# iupitter_v0_95_rev6_161019.net
KiCad netlist of a schematic drawn in EAGLE
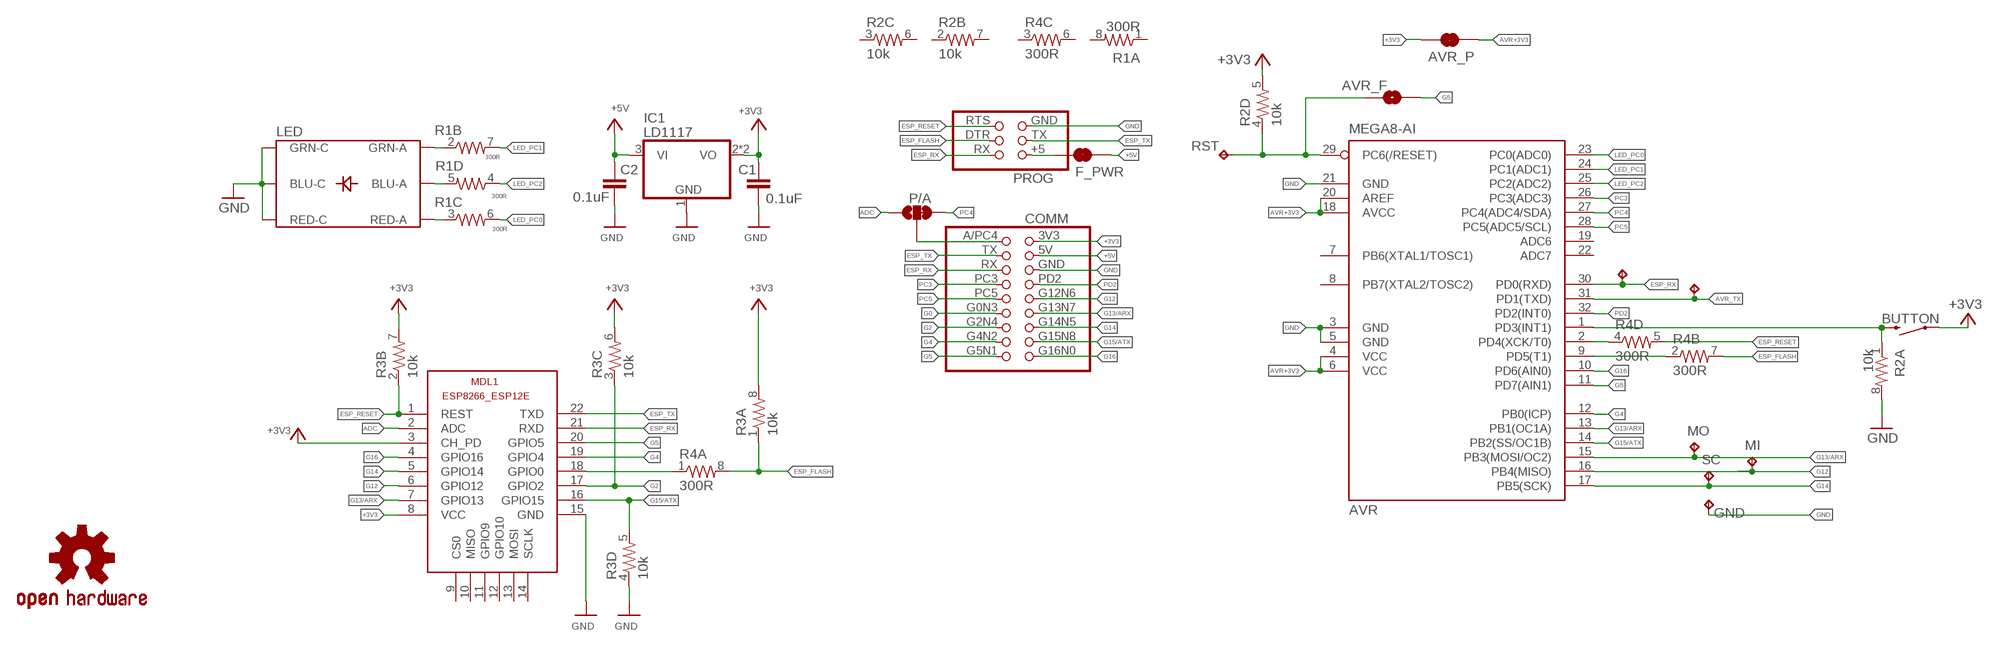
[diagram p0: schematic, sheet 1]

(export (version "E")
  (design (tool "Eeschema 10.0.6"))
  (components
    (comp (ref "ARX")
      (value "TPTP10SQ")
      (footprint "eagle-import:TP10SQ")
      (libsource (lib "eagle-import") (part "TPTP10SQ"))
    )
    (comp (ref "ATX")
      (value "TPTP10SQ")
      (footprint "eagle-import:TP10SQ")
      (libsource (lib "eagle-import") (part "TPTP10SQ"))
    )
    (comp (ref "AVR")
      (value "MEGA8-AI")
      (footprint "eagle-import:TQFP32-08")
      (fields (field (name "MPN") "ATMEGA8-16AU"))
      (libsource (lib "eagle-import") (part "MEGA8-AI"))
    )
    (comp (ref "AVR_F")
      (value "JUMPER-PAD-2-NOYES_SILK")
      (footprint "eagle-import:PAD-JUMPER-2-NO_YES_SILK")
      (libsource (lib "eagle-import") (part "JUMPER-PAD-2-NOYES_SILK"))
    )
    (comp (ref "AVR_P")
      (value "JUMPER-PAD-2-NC_BY_TRACE")
      (footprint "eagle-import:PAD-JUMPER-2-NC_BY_TRACE_YES_SILK")
      (libsource (lib "eagle-import") (part "JUMPER-PAD-2-NC_BY_TRACE"))
    )
    (comp (ref "BUTTON")
      (value "IT-1181A")
      (footprint "eagle-import:TACTILE-SWITCH-1101NE")
      (libsource (lib "eagle-import") (part "SWITCH-MOMENTARY-2SMD-1101NE"))
    )
    (comp (ref "C1")
      (value "0.1uF")
      (footprint "eagle-import:C1206")
      (libsource (lib "eagle-import") (part "C-EUC1206"))
    )
    (comp (ref "C2")
      (value "0.1uF")
      (footprint "eagle-import:C1206")
      (libsource (lib "eagle-import") (part "C-EUC1206"))
    )
    (comp (ref "COMM")
      (value "COMM_V2RIGHT")
      (footprint "eagle-import:COMM_V2_R(MAIN)")
      (libsource (lib "eagle-import") (part "COMM_V2RIGHT"))
    )
    (comp (ref "F_PWR")
      (value "JUMPER-PAD-2-NC_BY_TRACE")
      (footprint "eagle-import:PAD-JUMPER-2-NC_BY_TRACE_YES_SILK")
      (libsource (lib "eagle-import") (part "JUMPER-PAD-2-NC_BY_TRACE"))
    )
    (comp (ref "GND")
      (value "TPTP10SQ")
      (footprint "eagle-import:TP10SQ")
      (libsource (lib "eagle-import") (part "TPTP10SQ"))
    )
    (comp (ref "IC1")
      (value "LD1117")
      (footprint "eagle-import:SOT223")
      (libsource (lib "eagle-import") (part "LD1117"))
    )
    (comp (ref "LED")
      (value "LED-TRICOLOR-5050NO_IC")
      (footprint "eagle-import:LED-TRICOLOR-5050")
      (libsource (lib "eagle-import") (part "LED-TRICOLOR-5050NO_IC"))
    )
    (comp (ref "LOGO1")
      (value "OSHW-LOGOS-COPPER")
      (footprint "eagle-import:OSHW-LOGO-S_COPPER")
      (libsource (lib "eagle-import") (part "OSHW-LOGOS-COPPER"))
    )
    (comp (ref "MDL1")
      (value "ESP8266-12EESP8266-ESP12E")
      (footprint "eagle-import:ESP8266-ESP12E")
      (libsource (lib "eagle-import") (part "ESP8266-12EESP8266-ESP12E"))
    )
    (comp (ref "MI")
      (value "TPTP10SQ")
      (footprint "eagle-import:TP10SQ")
      (libsource (lib "eagle-import") (part "TPTP10SQ"))
    )
    (comp (ref "MO")
      (value "TPTP10SQ")
      (footprint "eagle-import:TP10SQ")
      (libsource (lib "eagle-import") (part "TPTP10SQ"))
    )
    (comp (ref "P/A")
      (value "JUMPER-PAD-3-2OF3_NC_BY_TRACE_SMALL")
      (footprint "eagle-import:PAD-JUMPER-3-2OF3_NC_BY_TRACE_YES_SILK_FULL_BOX")
      (libsource (lib "eagle-import") (part "JUMPER-PAD-3-2OF3_NC_BY_TRACE_SMALL"))
    )
    (comp (ref "PROG")
      (value "FLASH")
      (footprint "eagle-import:FLASH")
      (libsource (lib "eagle-import") (part "FLASH"))
    )
    (comp (ref "R1")
      (value "300R")
      (footprint "eagle-import:0603-ARV")
      (libsource (lib "eagle-import") (part "RESISTOR-ARRAY0603-ARV"))
    )
    (comp (ref "R2")
      (value "10k")
      (footprint "eagle-import:0603-ARV")
      (libsource (lib "eagle-import") (part "RESISTOR-ARRAY0603-ARV"))
    )
    (comp (ref "R3")
      (value "10k")
      (footprint "eagle-import:0603-ARV")
      (libsource (lib "eagle-import") (part "RESISTOR-ARRAY0603-ARV"))
    )
    (comp (ref "R4")
      (value "300R")
      (footprint "eagle-import:0603-ARV")
      (libsource (lib "eagle-import") (part "RESISTOR-ARRAY0603-ARV"))
    )
    (comp (ref "RST")
      (value "TPTP10SQ")
      (footprint "eagle-import:TP10SQ")
      (libsource (lib "eagle-import") (part "TPTP10SQ"))
    )
    (comp (ref "SC")
      (value "TPTP10SQ")
      (footprint "eagle-import:TP10SQ")
      (libsource (lib "eagle-import") (part "TPTP10SQ"))
    )
  )
  (nets
    (net (code "1") (name "+3V3") (class "Default")
      (node (ref "AVR_P") (pin "1") (pinfunction "1_1") (pintype "passive"))
      (node (ref "BUTTON") (pin "1") (pinfunction "1_1") (pintype "passive"))
      (node (ref "C1") (pin "1") (pinfunction "1_1") (pintype "passive"))
      (node (ref "COMM") (pin "3V3") (pinfunction "+3V3_3V3") (pintype "passive"))
      (node (ref "IC1") (pin "2") (pinfunction "VO_2") (pintype "passive"))
      (node (ref "IC1") (pin "4") (pinfunction "VO_4") (pintype "passive"))
      (node (ref "MDL1") (pin "3") (pinfunction "CH_PD_3") (pintype "bidirectional"))
      (node (ref "MDL1") (pin "8") (pinfunction "VCC_8") (pintype "bidirectional"))
      (node (ref "R2") (pin "5") (pinfunction "2_5") (pintype "passive"))
      (node (ref "R3") (pin "6") (pinfunction "2_6") (pintype "passive"))
      (node (ref "R3") (pin "7") (pinfunction "2_7") (pintype "passive"))
      (node (ref "R3") (pin "8") (pinfunction "2_8") (pintype "passive"))
    )
    (net (code "2") (name "+5V") (class "Default")
      (node (ref "C2") (pin "1") (pinfunction "1_1") (pintype "passive"))
      (node (ref "COMM") (pin "5V") (pinfunction "+5_5V") (pintype "passive"))
      (node (ref "F_PWR") (pin "2") (pinfunction "2_2") (pintype "passive"))
      (node (ref "IC1") (pin "3") (pinfunction "VI_3") (pintype "input"))
    )
    (net (code "3") (name "ADC") (class "Default")
      (node (ref "MDL1") (pin "2") (pinfunction "ADC_2") (pintype "bidirectional"))
      (node (ref "P/A") (pin "1") (pinfunction "1_1") (pintype "passive"))
    )
    (net (code "4") (name "AVR+3V3") (class "Default")
      (node (ref "AVR") (pin "18") (pinfunction "AVCC_18") (pintype "power_in"))
      (node (ref "AVR") (pin "20") (pinfunction "AREF_20") (pintype "passive"))
      (node (ref "AVR") (pin "4") (pinfunction "VCC_4") (pintype "power_in"))
      (node (ref "AVR") (pin "6") (pinfunction "VCC_6") (pintype "power_in"))
      (node (ref "AVR_P") (pin "2") (pinfunction "2_2") (pintype "passive"))
    )
    (net (code "5") (name "AVR_TX") (class "Default")
      (node (ref "ATX") (pin "TP") (pinfunction "TP_TP") (pintype "input"))
      (node (ref "AVR") (pin "31") (pinfunction "PD1(TXD)_31") (pintype "bidirectional"))
    )
    (net (code "6") (name "ESP_FLASH") (class "Default")
      (node (ref "PROG") (pin "DTR") (pinfunction "4_DTR") (pintype "passive"))
      (node (ref "R3") (pin "1") (pinfunction "1_1") (pintype "passive"))
      (node (ref "R4") (pin "7") (pinfunction "2_7") (pintype "passive"))
      (node (ref "R4") (pin "8") (pinfunction "2_8") (pintype "passive"))
    )
    (net (code "7") (name "ESP_RESET") (class "Default")
      (node (ref "MDL1") (pin "1") (pinfunction "REST_1") (pintype "bidirectional"))
      (node (ref "PROG") (pin "RTS") (pinfunction "6_RTS") (pintype "passive"))
      (node (ref "R3") (pin "2") (pinfunction "1_2") (pintype "passive"))
      (node (ref "R4") (pin "5") (pinfunction "2_5") (pintype "passive"))
    )
    (net (code "8") (name "ESP_RX") (class "Default")
      (node (ref "ARX") (pin "TP") (pinfunction "TP_TP") (pintype "input"))
      (node (ref "AVR") (pin "30") (pinfunction "PD0(RXD)_30") (pintype "bidirectional"))
      (node (ref "COMM") (pin "RX") (pinfunction "RX_RX") (pintype "passive"))
      (node (ref "MDL1") (pin "21") (pinfunction "RXD_21") (pintype "bidirectional"))
      (node (ref "PROG") (pin "RX") (pinfunction "2_RX") (pintype "passive"))
    )
    (net (code "9") (name "ESP_TX") (class "Default")
      (node (ref "COMM") (pin "TX") (pinfunction "TX_TX") (pintype "passive"))
      (node (ref "MDL1") (pin "22") (pinfunction "TXD_22") (pintype "bidirectional"))
      (node (ref "PROG") (pin "TX") (pinfunction "3_TX") (pintype "passive"))
    )
    (net (code "10") (name "G0") (class "Default")
      (node (ref "COMM") (pin "G0N3") (pinfunction "G0N3_G0N3") (pintype "passive"))
      (node (ref "MDL1") (pin "18") (pinfunction "GPIO0_18") (pintype "bidirectional"))
      (node (ref "R4") (pin "1") (pinfunction "1_1") (pintype "passive"))
    )
    (net (code "11") (name "G2") (class "Default")
      (node (ref "COMM") (pin "G2N4") (pinfunction "G2N4_G2N4") (pintype "passive"))
      (node (ref "MDL1") (pin "17") (pinfunction "GPIO2_17") (pintype "bidirectional"))
      (node (ref "R3") (pin "3") (pinfunction "1_3") (pintype "passive"))
    )
    (net (code "12") (name "G4") (class "Default")
      (node (ref "AVR") (pin "12") (pinfunction "PB0(ICP)_12") (pintype "bidirectional"))
      (node (ref "COMM") (pin "G4N2") (pinfunction "G4N2_G4N2") (pintype "passive"))
      (node (ref "MDL1") (pin "19") (pinfunction "GPIO4_19") (pintype "bidirectional"))
    )
    (net (code "13") (name "G5") (class "Default")
      (node (ref "AVR") (pin "11") (pinfunction "PD7(AIN1)_11") (pintype "bidirectional"))
      (node (ref "AVR_F") (pin "2") (pinfunction "2_2") (pintype "passive"))
      (node (ref "COMM") (pin "G5N1") (pinfunction "G5N1_G5N1") (pintype "passive"))
      (node (ref "MDL1") (pin "20") (pinfunction "GPIO5_20") (pintype "bidirectional"))
    )
    (net (code "14") (name "G12") (class "Default")
      (node (ref "AVR") (pin "16") (pinfunction "PB4(MISO)_16") (pintype "bidirectional"))
      (node (ref "COMM") (pin "G12N6") (pinfunction "G12N6_G12N6") (pintype "passive"))
      (node (ref "MDL1") (pin "6") (pinfunction "GPIO12_6") (pintype "bidirectional"))
      (node (ref "MI") (pin "TP") (pinfunction "TP_TP") (pintype "input"))
    )
    (net (code "15") (name "G13{slash}ARX") (class "Default")
      (node (ref "AVR") (pin "13") (pinfunction "PB1(OC1A)_13") (pintype "bidirectional"))
      (node (ref "AVR") (pin "15") (pinfunction "PB3(MOSI/OC2)_15") (pintype "bidirectional"))
      (node (ref "COMM") (pin "G13N7") (pinfunction "G13N7_G13N7") (pintype "passive"))
      (node (ref "MDL1") (pin "7") (pinfunction "GPIO13_7") (pintype "bidirectional"))
      (node (ref "MO") (pin "TP") (pinfunction "TP_TP") (pintype "input"))
    )
    (net (code "16") (name "G14") (class "Default")
      (node (ref "AVR") (pin "17") (pinfunction "PB5(SCK)_17") (pintype "bidirectional"))
      (node (ref "COMM") (pin "G14N5") (pinfunction "G14N5_G14N5") (pintype "passive"))
      (node (ref "MDL1") (pin "5") (pinfunction "GPIO14_5") (pintype "bidirectional"))
      (node (ref "SC") (pin "TP") (pinfunction "TP_TP") (pintype "input"))
    )
    (net (code "17") (name "G15{slash}ATX") (class "Default")
      (node (ref "AVR") (pin "14") (pinfunction "PB2(SS/OC1B)_14") (pintype "bidirectional"))
      (node (ref "COMM") (pin "G15N8") (pinfunction "G15N8_G15N8") (pintype "passive"))
      (node (ref "MDL1") (pin "16") (pinfunction "GPIO15_16") (pintype "bidirectional"))
      (node (ref "R3") (pin "5") (pinfunction "2_5") (pintype "passive"))
    )
    (net (code "18") (name "G16") (class "Default")
      (node (ref "AVR") (pin "10") (pinfunction "PD6(AIN0)_10") (pintype "bidirectional"))
      (node (ref "COMM") (pin "G16N0") (pinfunction "G16N0_G16N0") (pintype "passive"))
      (node (ref "MDL1") (pin "4") (pinfunction "GPIO16_4") (pintype "bidirectional"))
    )
    (net (code "19") (name "GND") (class "Default")
      (node (ref "AVR") (pin "21") (pinfunction "GND_21") (pintype "power_in"))
      (node (ref "AVR") (pin "3") (pinfunction "GND_3") (pintype "power_in"))
      (node (ref "AVR") (pin "5") (pinfunction "GND_5") (pintype "power_in"))
      (node (ref "C1") (pin "2") (pinfunction "2_2") (pintype "passive"))
      (node (ref "C2") (pin "2") (pinfunction "2_2") (pintype "passive"))
      (node (ref "COMM") (pin "GND") (pinfunction "GND_GND") (pintype "passive"))
      (node (ref "GND") (pin "TP") (pinfunction "TP_TP") (pintype "input"))
      (node (ref "IC1") (pin "1") (pinfunction "GND_1") (pintype "passive"))
      (node (ref "LED") (pin "4") (pinfunction "GRN-C_4") (pintype "bidirectional"))
      (node (ref "LED") (pin "5") (pinfunction "RED-C_5") (pintype "bidirectional"))
      (node (ref "LED") (pin "6") (pinfunction "BLU-C_6") (pintype "bidirectional"))
      (node (ref "MDL1") (pin "15") (pinfunction "GND_15") (pintype "bidirectional"))
      (node (ref "PROG") (pin "GND") (pinfunction "5_GND") (pintype "passive"))
      (node (ref "R2") (pin "8") (pinfunction "2_8") (pintype "passive"))
      (node (ref "R3") (pin "4") (pinfunction "1_4") (pintype "passive"))
    )
    (net (code "20") (name "LED_PC0") (class "Default")
      (node (ref "AVR") (pin "23") (pinfunction "PC0(ADC0)_23") (pintype "bidirectional"))
      (node (ref "R1") (pin "6") (pinfunction "2_6") (pintype "passive"))
    )
    (net (code "21") (name "LED_PC1") (class "Default")
      (node (ref "AVR") (pin "24") (pinfunction "PC1(ADC1)_24") (pintype "bidirectional"))
      (node (ref "R1") (pin "7") (pinfunction "2_7") (pintype "passive"))
    )
    (net (code "22") (name "LED_PC2") (class "Default")
      (node (ref "AVR") (pin "25") (pinfunction "PC2(ADC2)_25") (pintype "bidirectional"))
      (node (ref "R1") (pin "4") (pinfunction "1_4") (pintype "passive"))
    )
    (net (code "23") (name "Net-(AVR-PC6({slash}RESET))") (class "Default")
      (node (ref "AVR") (pin "29") (pinfunction "PC6(/RESET)_29") (pintype "bidirectional"))
      (node (ref "AVR_F") (pin "1") (pinfunction "1_1") (pintype "passive"))
      (node (ref "R2") (pin "4") (pinfunction "1_4") (pintype "passive"))
      (node (ref "RST") (pin "TP") (pinfunction "TP_TP") (pintype "input"))
    )
    (net (code "24") (name "Net-(AVR-PD3(INT1))") (class "Default")
      (node (ref "AVR") (pin "1") (pinfunction "PD3(INT1)_1") (pintype "bidirectional"))
      (node (ref "BUTTON") (pin "2") (pinfunction "2_2") (pintype "passive"))
      (node (ref "R2") (pin "1") (pinfunction "1_1") (pintype "passive"))
    )
    (net (code "25") (name "Net-(AVR-PD4(XCK{slash}T0))") (class "Default")
      (node (ref "AVR") (pin "2") (pinfunction "PD4(XCK/T0)_2") (pintype "bidirectional"))
      (node (ref "R4") (pin "4") (pinfunction "1_4") (pintype "passive"))
    )
    (net (code "26") (name "Net-(AVR-PD5(T1))") (class "Default")
      (node (ref "AVR") (pin "9") (pinfunction "PD5(T1)_9") (pintype "bidirectional"))
      (node (ref "R4") (pin "2") (pinfunction "1_2") (pintype "passive"))
    )
    (net (code "27") (name "Net-(COMM-ADC_PC4)") (class "Default")
      (node (ref "COMM") (pin "A/PC4") (pinfunction "ADC_PC4_A/PC4") (pintype "passive"))
      (node (ref "P/A") (pin "2") (pinfunction "2_2") (pintype "passive"))
    )
    (net (code "28") (name "Net-(LED-BLU-A)") (class "Default")
      (node (ref "LED") (pin "1") (pinfunction "BLU-A_1") (pintype "bidirectional"))
      (node (ref "R1") (pin "5") (pinfunction "2_5") (pintype "passive"))
    )
    (net (code "29") (name "Net-(LED-GRN-A)") (class "Default")
      (node (ref "LED") (pin "3") (pinfunction "GRN-A_3") (pintype "bidirectional"))
      (node (ref "R1") (pin "2") (pinfunction "1_2") (pintype "passive"))
    )
    (net (code "30") (name "Net-(LED-RED-A)") (class "Default")
      (node (ref "LED") (pin "2") (pinfunction "RED-A_2") (pintype "bidirectional"))
      (node (ref "R1") (pin "3") (pinfunction "1_3") (pintype "passive"))
    )
    (net (code "31") (name "Net-(PROG-1)") (class "Default")
      (node (ref "F_PWR") (pin "1") (pinfunction "1_1") (pintype "passive"))
      (node (ref "PROG") (pin "+5") (pinfunction "1_+5") (pintype "passive"))
    )
    (net (code "32") (name "PC3") (class "Default")
      (node (ref "AVR") (pin "26") (pinfunction "PC3(ADC3)_26") (pintype "bidirectional"))
      (node (ref "COMM") (pin "PC3") (pinfunction "PC3_PC3") (pintype "passive"))
    )
    (net (code "33") (name "PC4") (class "Default")
      (node (ref "AVR") (pin "27") (pinfunction "PC4(ADC4/SDA)_27") (pintype "bidirectional"))
      (node (ref "P/A") (pin "3") (pinfunction "3_3") (pintype "passive"))
    )
    (net (code "34") (name "PC5") (class "Default")
      (node (ref "AVR") (pin "28") (pinfunction "PC5(ADC5/SCL)_28") (pintype "bidirectional"))
      (node (ref "COMM") (pin "PC5") (pinfunction "PC4_PC5") (pintype "passive"))
    )
    (net (code "35") (name "PD2") (class "Default")
      (node (ref "AVR") (pin "32") (pinfunction "PD2(INT0)_32") (pintype "bidirectional"))
      (node (ref "COMM") (pin "PD2") (pinfunction "PD2_PD2") (pintype "passive"))
    )
    (net (code "36") (name "unconnected-(AVR-ADC6-Pad19)") (class "Default")
      (node (ref "AVR") (pin "19") (pinfunction "ADC6_19") (pintype "bidirectional"))
    )
    (net (code "37") (name "unconnected-(AVR-ADC7-Pad22)") (class "Default")
      (node (ref "AVR") (pin "22") (pinfunction "ADC7_22") (pintype "bidirectional"))
    )
    (net (code "38") (name "unconnected-(AVR-PB6(XTAL1{slash}TOSC1)-Pad7)") (class "Default")
      (node (ref "AVR") (pin "7") (pinfunction "PB6(XTAL1/TOSC1)_7") (pintype "bidirectional"))
    )
    (net (code "39") (name "unconnected-(AVR-PB7(XTAL2{slash}TOSC2)-Pad8)") (class "Default")
      (node (ref "AVR") (pin "8") (pinfunction "PB7(XTAL2/TOSC2)_8") (pintype "bidirectional"))
    )
    (net (code "40") (name "unconnected-(MDL1-CS0-Pad9)") (class "Default")
      (node (ref "MDL1") (pin "9") (pinfunction "CS0_9") (pintype "bidirectional"))
    )
    (net (code "41") (name "unconnected-(MDL1-GPIO9-Pad11)") (class "Default")
      (node (ref "MDL1") (pin "11") (pinfunction "GPIO9_11") (pintype "bidirectional"))
    )
    (net (code "42") (name "unconnected-(MDL1-GPIO10-Pad12)") (class "Default")
      (node (ref "MDL1") (pin "12") (pinfunction "GPIO10_12") (pintype "bidirectional"))
    )
    (net (code "43") (name "unconnected-(MDL1-MISO-Pad10)") (class "Default")
      (node (ref "MDL1") (pin "10") (pinfunction "MISO_10") (pintype "bidirectional"))
    )
    (net (code "44") (name "unconnected-(MDL1-MOSI-Pad13)") (class "Default")
      (node (ref "MDL1") (pin "13") (pinfunction "MOSI_13") (pintype "bidirectional"))
    )
    (net (code "45") (name "unconnected-(MDL1-SCLK-Pad14)") (class "Default")
      (node (ref "MDL1") (pin "14") (pinfunction "SCLK_14") (pintype "bidirectional"))
    )
    (net (code "46") (name "unconnected-(R1-Pad1)") (class "Default")
      (node (ref "R1") (pin "1") (pinfunction "1_1") (pintype "passive"))
    )
    (net (code "47") (name "unconnected-(R1A-2-Pad8)") (class "Default")
      (node (ref "R1") (pin "8") (pinfunction "2_8") (pintype "passive"))
    )
    (net (code "48") (name "unconnected-(R2B-1-Pad2)") (class "Default")
      (node (ref "R2") (pin "2") (pinfunction "1_2") (pintype "passive"))
    )
    (net (code "49") (name "unconnected-(R2B-2-Pad7)") (class "Default")
      (node (ref "R2") (pin "7") (pinfunction "2_7") (pintype "passive"))
    )
    (net (code "50") (name "unconnected-(R2C-1-Pad3)") (class "Default")
      (node (ref "R2") (pin "3") (pinfunction "1_3") (pintype "passive"))
    )
    (net (code "51") (name "unconnected-(R2C-2-Pad6)") (class "Default")
      (node (ref "R2") (pin "6") (pinfunction "2_6") (pintype "passive"))
    )
    (net (code "52") (name "unconnected-(R4C-1-Pad3)") (class "Default")
      (node (ref "R4") (pin "3") (pinfunction "1_3") (pintype "passive"))
    )
    (net (code "53") (name "unconnected-(R4C-2-Pad6)") (class "Default")
      (node (ref "R4") (pin "6") (pinfunction "2_6") (pintype "passive"))
    )
  )
)
